# Power.net
KiCad netlist of a schematic drawn in Altium Designer
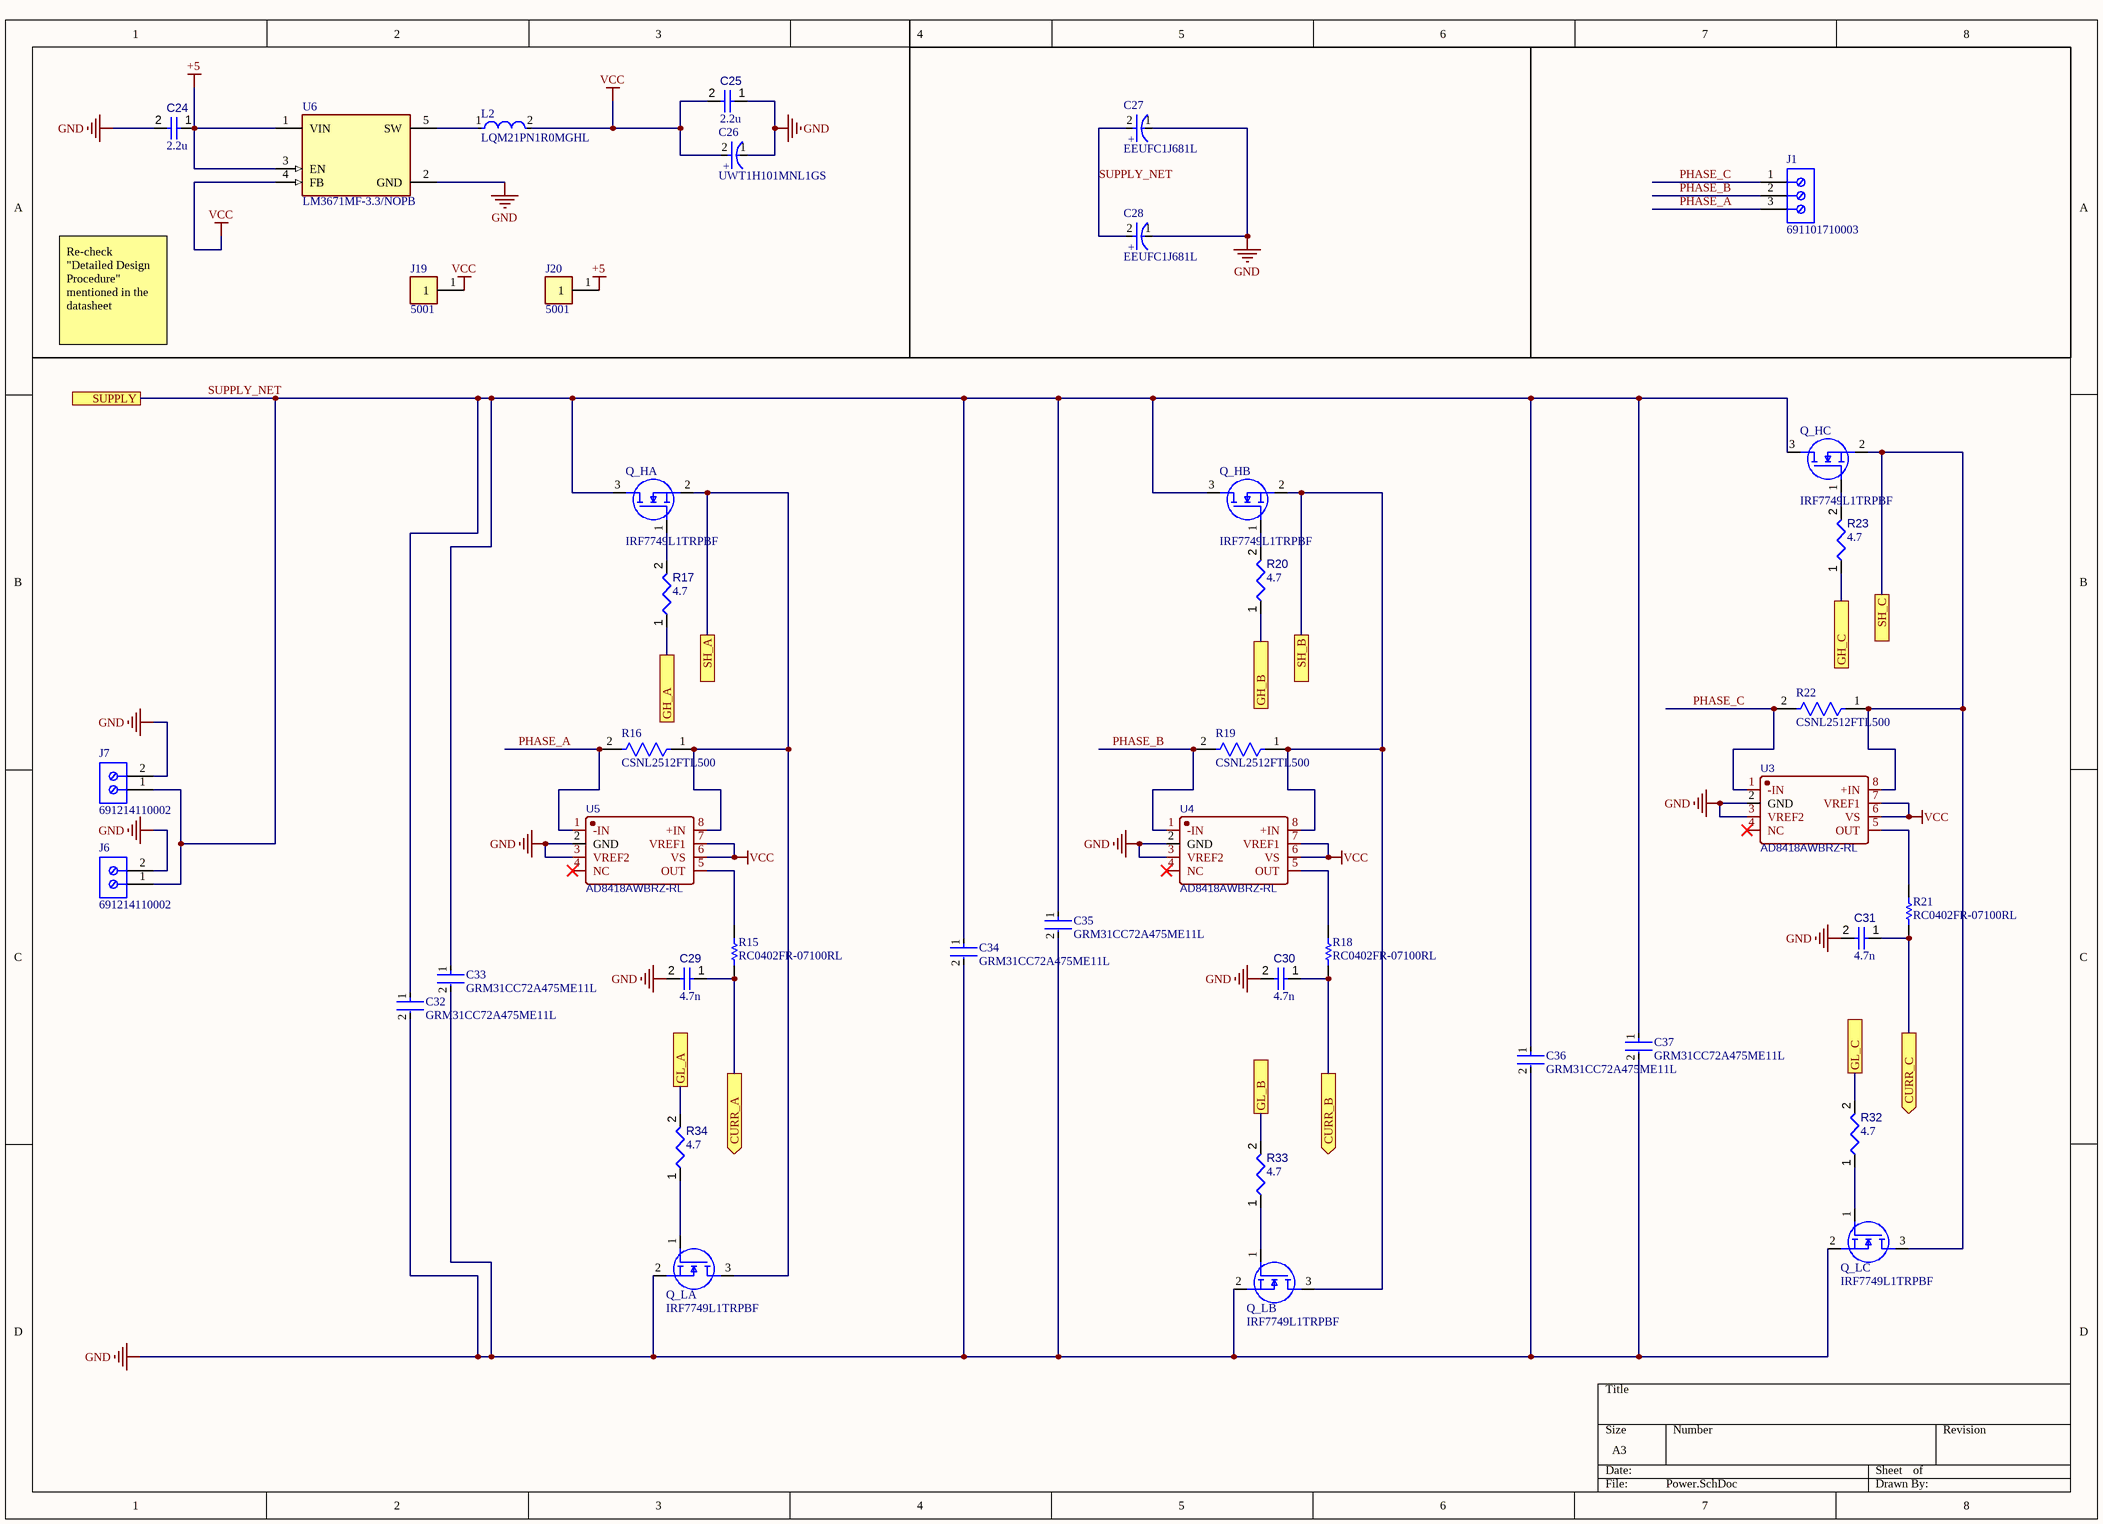
[diagram p0: Power.SchDoc]

(export (version "E")
  (design (tool "Eeschema 10.0.6"))
  (components
    (comp (ref "C24")
      (value "2.2u")
      (footprint "CAP-0805")
      (description "ESD SMD Comm X7R 0805 (2012Metric) Ceramic Capacitor 0.079Lx0.049W 2.00mmx1.25mm X7R ±5% 2.2muF")
      (fields (field (name "Comment") "C0805C225J4REC7800"))
      (libsource (lib "University of Michigan") (part "CAP-NP-2"))
    )
    (comp (ref "C25")
      (value "2.2u")
      (footprint "CAP-0805")
      (description "ESD SMD Comm X7R 0805 (2012Metric) Ceramic Capacitor 0.079Lx0.049W 2.00mmx1.25mm X7R ±5% 2.2muF")
      (fields (field (name "Comment") "C0805C225J4REC7800"))
      (libsource (lib "University of Michigan") (part "CAP-NP-2"))
    )
    (comp (ref "C26")
      (value "UWT1H101MNL1GS")
      (footprint "FP-UWT1H101MNL1GS-MFG")
      (description "CAP ALUM 100UF 20% 50V SMD")
      (fields (field (name "TOLERANCE") "20%") (field (name "VOLTAGE") "50V"))
      (libsource (lib "Altium Content Vault") (part "203bc49f2ac43e59fd269a8c329ed05"))
    )
    (comp (ref "C27")
      (value "EEUFC1J681L")
      (footprint "FP-EEUFC1J681L-MFG")
      (description "CAP ALUM 680UF 20% 63V RADIAL")
      (fields
        (field (name "MANUFACTURER") "Panasonic")
        (field (name "OCTOPART") "https://octopart.com/eeu-fc1j681l-panasonic-39478579")
      )
      (libsource (lib "Altium Content Vault") (part "cf48714ba7e38822c1575c7ec0b6d1f"))
    )
    (comp (ref "C28")
      (value "EEUFC1J681L")
      (footprint "FP-EEUFC1J681L-MFG")
      (description "CAP ALUM 680UF 20% 63V RADIAL")
      (fields
        (field (name "MANUFACTURER") "Panasonic")
        (field (name "OCTOPART") "https://octopart.com/eeu-fc1j681l-panasonic-39478579")
      )
      (libsource (lib "Altium Content Vault") (part "cf48714ba7e38822c1575c7ec0b6d1f"))
    )
    (comp (ref "C29")
      (value "4.7n")
      (footprint "CAP-0402")
      (fields (field (name "Comment") "C0402C472K4RECAUTO"))
      (libsource (lib "University of Michigan") (part "CAP-NP-2"))
    )
    (comp (ref "C30")
      (value "4.7n")
      (footprint "CAP-0402")
      (fields (field (name "Comment") "C0402C472K4RECAUTO"))
      (libsource (lib "University of Michigan") (part "CAP-NP-2"))
    )
    (comp (ref "C31")
      (value "4.7n")
      (footprint "CAP-0402")
      (fields (field (name "Comment") "C0402C472K4RECAUTO"))
      (libsource (lib "University of Michigan") (part "CAP-NP-2"))
    )
    (comp (ref "C32")
      (value "GRM31CC72A475ME11L")
      (footprint "FP-GRM31C-0_3-e0_3_0_9-MFG")
      (description "Chip Multilayer Ceramic Capacitors for General Purpose, 1206, 4.7uF, X7S, 22%, 20%, 100V")
      (libsource (lib "Altium Content Vault") (part "11868f565c42a9108669ba33697ecf6"))
    )
    (comp (ref "C33")
      (value "GRM31CC72A475ME11L")
      (footprint "FP-GRM31C-0_3-e0_3_0_9-MFG")
      (description "Chip Multilayer Ceramic Capacitors for General Purpose, 1206, 4.7uF, X7S, 22%, 20%, 100V")
      (libsource (lib "Altium Content Vault") (part "11868f565c42a9108669ba33697ecf6"))
    )
    (comp (ref "C34")
      (value "GRM31CC72A475ME11L")
      (footprint "FP-GRM31C-0_3-e0_3_0_9-MFG")
      (description "Chip Multilayer Ceramic Capacitors for General Purpose, 1206, 4.7uF, X7S, 22%, 20%, 100V")
      (libsource (lib "Altium Content Vault") (part "11868f565c42a9108669ba33697ecf6"))
    )
    (comp (ref "C35")
      (value "GRM31CC72A475ME11L")
      (footprint "FP-GRM31C-0_3-e0_3_0_9-MFG")
      (description "Chip Multilayer Ceramic Capacitors for General Purpose, 1206, 4.7uF, X7S, 22%, 20%, 100V")
      (libsource (lib "Altium Content Vault") (part "11868f565c42a9108669ba33697ecf6"))
    )
    (comp (ref "C36")
      (value "GRM31CC72A475ME11L")
      (footprint "FP-GRM31C-0_3-e0_3_0_9-MFG")
      (description "Chip Multilayer Ceramic Capacitors for General Purpose, 1206, 4.7uF, X7S, 22%, 20%, 100V")
      (libsource (lib "Altium Content Vault") (part "11868f565c42a9108669ba33697ecf6"))
    )
    (comp (ref "C37")
      (value "GRM31CC72A475ME11L")
      (footprint "FP-GRM31C-0_3-e0_3_0_9-MFG")
      (description "Chip Multilayer Ceramic Capacitors for General Purpose, 1206, 4.7uF, X7S, 22%, 20%, 100V")
      (libsource (lib "Altium Content Vault") (part "11868f565c42a9108669ba33697ecf6"))
    )
    (comp (ref "J1")
      (value "691101710003")
      (footprint "691101710003")
      (fields (field (name "VOLTAGE") "250V"))
      (libsource (lib "Altium Content Vault") (part "TBL - 1R - 03P - Screw"))
    )
    (comp (ref "J6")
      (value "691214110002")
      (footprint "691214110002")
      (fields (field (name "VOLTAGE") "300V"))
      (libsource (lib "Altium Content Vault") (part "TBL - 1R - 02P - Screw"))
    )
    (comp (ref "J7")
      (value "691214110002")
      (footprint "691214110002")
      (fields (field (name "VOLTAGE") "300V"))
      (libsource (lib "Altium Content Vault") (part "TBL - 1R - 02P - Screw"))
    )
    (comp (ref "J19")
      (value "5001")
      (footprint "FP-5001-MFG")
      (description "PC TEST POINT MINIATURE BLACK")
      (libsource (lib "Altium Content Vault") (part "1e4615820a309e3ce90f9e6d957b7fa"))
    )
    (comp (ref "J20")
      (value "5001")
      (footprint "FP-5001-MFG")
      (description "PC TEST POINT MINIATURE BLACK")
      (libsource (lib "Altium Content Vault") (part "1e4615820a309e3ce90f9e6d957b7fa"))
    )
    (comp (ref "L2")
      (value "LQM21PN1R0MGHL")
      (footprint "FP-LQM21PH_G0-MFG")
      (description "Multilayer Type Inductor for Power Lines, 0805 (2012), 1μH, 20%, 0.1Ω, 2A")
      (fields (field (name "TOLERANCE") "20%"))
      (libsource (lib "Altium Content Vault") (part "725321dda6339637d4d059423bc1c3c"))
    )
    (comp (ref "Q_HA")
      (value "IRF7749L1TRPBF")
      (footprint "IC-MOSFET-DirectFET")
      (description "Power Field-Effect Transistor, 375A I(D), 1-Element, N-Channel, Metal-oxide Semiconductor FET")
      (libsource (lib "University of Michigan") (part "NMOS-200MA-0001"))
    )
    (comp (ref "Q_HB")
      (value "IRF7749L1TRPBF")
      (footprint "IC-MOSFET-DirectFET")
      (description "Power Field-Effect Transistor, 375A I(D), 1-Element, N-Channel, Metal-oxide Semiconductor FET")
      (libsource (lib "University of Michigan") (part "NMOS-200MA-0001"))
    )
    (comp (ref "Q_HC")
      (value "IRF7749L1TRPBF")
      (footprint "IC-MOSFET-DirectFET")
      (description "Power Field-Effect Transistor, 375A I(D), 1-Element, N-Channel, Metal-oxide Semiconductor FET")
      (libsource (lib "University of Michigan") (part "NMOS-200MA-0001"))
    )
    (comp (ref "Q_LA")
      (value "IRF7749L1TRPBF")
      (footprint "IC-MOSFET-DirectFET")
      (description "Power Field-Effect Transistor, 375A I(D), 1-Element, N-Channel, Metal-oxide Semiconductor FET")
      (libsource (lib "University of Michigan") (part "NMOS-200MA-0001"))
    )
    (comp (ref "Q_LB")
      (value "IRF7749L1TRPBF")
      (footprint "IC-MOSFET-DirectFET")
      (description "Power Field-Effect Transistor, 375A I(D), 1-Element, N-Channel, Metal-oxide Semiconductor FET")
      (libsource (lib "University of Michigan") (part "NMOS-200MA-0001"))
    )
    (comp (ref "Q_LC")
      (value "IRF7749L1TRPBF")
      (footprint "IC-MOSFET-DirectFET")
      (description "Power Field-Effect Transistor, 375A I(D), 1-Element, N-Channel, Metal-oxide Semiconductor FET")
      (libsource (lib "University of Michigan") (part "NMOS-200MA-0001"))
    )
    (comp (ref "R15")
      (value "RC0402FR-07100RL")
      (footprint "RESC1005X40X25ML05T10")
      (fields (field (name "MANUFACTURER") "Yageo / Phycomp"))
      (libsource (lib "Altium Content Vault") (part "RES"))
    )
    (comp (ref "R16")
      (value "CSNL2512FTL500")
      (footprint "FP-CSNL2512FTL500-MFG")
      (description "RES 500 UOHM 1% 2W 2512")
      (fields (field (name "TOLERANCE") "1%"))
      (libsource (lib "Altium Content Vault") (part "1029c3af85768c4190bb7ad29bc67b5"))
    )
    (comp (ref "R17")
      (value "4.7")
      (footprint "RES-0603")
      (fields
        (field (name "POWER") "250mW")
        (field (name "TOLERANCE") "5%")
        (field (name "Comment") "CRCW06034R70JNEAHP")
      )
      (libsource (lib "University of Michigan") (part "RES-2"))
    )
    (comp (ref "R18")
      (value "RC0402FR-07100RL")
      (footprint "RESC1005X40X25ML05T10")
      (fields (field (name "MANUFACTURER") "Yageo / Phycomp"))
      (libsource (lib "Altium Content Vault") (part "RES"))
    )
    (comp (ref "R19")
      (value "CSNL2512FTL500")
      (footprint "FP-CSNL2512FTL500-MFG")
      (description "RES 500 UOHM 1% 2W 2512")
      (fields (field (name "TOLERANCE") "1%"))
      (libsource (lib "Altium Content Vault") (part "1029c3af85768c4190bb7ad29bc67b5"))
    )
    (comp (ref "R20")
      (value "4.7")
      (footprint "RES-0603")
      (fields
        (field (name "POWER") "250mW")
        (field (name "TOLERANCE") "5%")
        (field (name "Comment") "CRCW06034R70JNEAHP")
      )
      (libsource (lib "University of Michigan") (part "RES-2"))
    )
    (comp (ref "R21")
      (value "RC0402FR-07100RL")
      (footprint "RESC1005X40X25ML05T10")
      (fields (field (name "MANUFACTURER") "Yageo / Phycomp"))
      (libsource (lib "Altium Content Vault") (part "RES"))
    )
    (comp (ref "R22")
      (value "CSNL2512FTL500")
      (footprint "FP-CSNL2512FTL500-MFG")
      (description "RES 500 UOHM 1% 2W 2512")
      (fields (field (name "TOLERANCE") "1%"))
      (libsource (lib "Altium Content Vault") (part "1029c3af85768c4190bb7ad29bc67b5"))
    )
    (comp (ref "R23")
      (value "4.7")
      (footprint "RES-0603")
      (fields
        (field (name "POWER") "250mW")
        (field (name "TOLERANCE") "5%")
        (field (name "Comment") "CRCW06034R70JNEAHP")
      )
      (libsource (lib "University of Michigan") (part "RES-2"))
    )
    (comp (ref "R32")
      (value "4.7")
      (footprint "RES-0603")
      (fields
        (field (name "POWER") "250mW")
        (field (name "TOLERANCE") "5%")
        (field (name "Comment") "CRCW06034R70JNEAHP")
      )
      (libsource (lib "University of Michigan") (part "RES-2"))
    )
    (comp (ref "R33")
      (value "4.7")
      (footprint "RES-0603")
      (fields
        (field (name "POWER") "250mW")
        (field (name "TOLERANCE") "5%")
        (field (name "Comment") "CRCW06034R70JNEAHP")
      )
      (libsource (lib "University of Michigan") (part "RES-2"))
    )
    (comp (ref "R34")
      (value "4.7")
      (footprint "RES-0603")
      (fields
        (field (name "POWER") "250mW")
        (field (name "TOLERANCE") "5%")
        (field (name "Comment") "CRCW06034R70JNEAHP")
      )
      (libsource (lib "University of Michigan") (part "RES-2"))
    )
    (comp (ref "U3")
      (value "AD8418AWBRZ-RL")
      (footprint "MasterLib:IC-SOIC8")
      (fields (field (name "MANUFACTURER") "Analog Devices") (field (name "CONTRIBUTOR") "LCSC"))
      (libsource (lib "altium-import") (part "root_0_AD8418AWBRZ-RL_"))
    )
    (comp (ref "U4")
      (value "AD8418AWBRZ-RL")
      (footprint "MasterLib:IC-SOIC8")
      (fields (field (name "MANUFACTURER") "Analog Devices") (field (name "CONTRIBUTOR") "LCSC"))
      (libsource (lib "altium-import") (part "root_0_AD8418AWBRZ-RL_"))
    )
    (comp (ref "U5")
      (value "AD8418AWBRZ-RL")
      (footprint "MasterLib:IC-SOIC8")
      (fields (field (name "MANUFACTURER") "Analog Devices") (field (name "CONTRIBUTOR") "LCSC"))
      (libsource (lib "altium-import") (part "root_0_AD8418AWBRZ-RL_"))
    )
    (comp (ref "U6")
      (value "LM3671MF-3.3/NOPB")
      (footprint "FP-DBV0005A-IPC_C")
      (description "IC REG BUCK 3.3V 600MA SOT23-5")
      (libsource (lib "Altium Content Vault") (part "6d197bdb01e3056b44211661dc106cd"))
    )
  )
  (nets
    (net (code "1") (name "+5") (class "Default")
      (node (ref "C24") (pin "1") (pinfunction "1_1") (pintype "passive"))
      (node (ref "J20") (pin "1") (pinfunction "1_1") (pintype "passive"))
      (node (ref "U6") (pin "1") (pinfunction "VIN_1") (pintype "power_in"))
      (node (ref "U6") (pin "3") (pinfunction "EN_3") (pintype "input"))
    )
    (net (code "2") (name "/CURR_A") (class "Default")
      (node (ref "C29") (pin "1") (pinfunction "1_1") (pintype "passive"))
      (node (ref "R15") (pin "1") (pinfunction "1_1") (pintype "passive"))
    )
    (net (code "3") (name "/CURR_B") (class "Default")
      (node (ref "C30") (pin "1") (pinfunction "1_1") (pintype "passive"))
      (node (ref "R18") (pin "1") (pinfunction "1_1") (pintype "passive"))
    )
    (net (code "4") (name "/CURR_C") (class "Default")
      (node (ref "C31") (pin "1") (pinfunction "1_1") (pintype "passive"))
      (node (ref "R21") (pin "1") (pinfunction "1_1") (pintype "passive"))
    )
    (net (code "5") (name "/GH_A") (class "Default")
      (node (ref "R17") (pin "1") (pinfunction "1_1") (pintype "passive"))
    )
    (net (code "6") (name "/GH_B") (class "Default")
      (node (ref "R20") (pin "1") (pinfunction "1_1") (pintype "passive"))
    )
    (net (code "7") (name "/GH_C") (class "Default")
      (node (ref "R23") (pin "1") (pinfunction "1_1") (pintype "passive"))
    )
    (net (code "8") (name "/GL_A") (class "Default")
      (node (ref "R34") (pin "2") (pinfunction "2_2") (pintype "passive"))
    )
    (net (code "9") (name "/GL_B") (class "Default")
      (node (ref "R33") (pin "2") (pinfunction "2_2") (pintype "passive"))
    )
    (net (code "10") (name "/GL_C") (class "Default")
      (node (ref "R32") (pin "2") (pinfunction "2_2") (pintype "passive"))
    )
    (net (code "11") (name "/PHASE_A") (class "Default")
      (node (ref "J1") (pin "3") (pinfunction "3_3") (pintype "passive"))
      (node (ref "R16") (pin "2") (pinfunction "2_2") (pintype "passive"))
      (node (ref "U5") (pin "1") (pinfunction "-IN_1") (pintype "passive"))
    )
    (net (code "12") (name "/PHASE_B") (class "Default")
      (node (ref "J1") (pin "2") (pinfunction "2_2") (pintype "passive"))
      (node (ref "R19") (pin "2") (pinfunction "2_2") (pintype "passive"))
      (node (ref "U4") (pin "1") (pinfunction "-IN_1") (pintype "passive"))
    )
    (net (code "13") (name "/PHASE_C") (class "Default")
      (node (ref "J1") (pin "1") (pinfunction "1_1") (pintype "passive"))
      (node (ref "R22") (pin "2") (pinfunction "2_2") (pintype "passive"))
      (node (ref "U3") (pin "1") (pinfunction "-IN_1") (pintype "passive"))
    )
    (net (code "14") (name "/SH_A") (class "Default")
      (node (ref "Q_HA") (pin "2") (pinfunction "S_2") (pintype "passive"))
      (node (ref "Q_LA") (pin "3") (pinfunction "D_3") (pintype "passive"))
      (node (ref "R16") (pin "1") (pinfunction "1_1") (pintype "passive"))
      (node (ref "U5") (pin "8") (pinfunction "+IN_8") (pintype "passive"))
    )
    (net (code "15") (name "/SH_B") (class "Default")
      (node (ref "Q_HB") (pin "2") (pinfunction "S_2") (pintype "passive"))
      (node (ref "Q_LB") (pin "3") (pinfunction "D_3") (pintype "passive"))
      (node (ref "R19") (pin "1") (pinfunction "1_1") (pintype "passive"))
      (node (ref "U4") (pin "8") (pinfunction "+IN_8") (pintype "passive"))
    )
    (net (code "16") (name "/SH_C") (class "Default")
      (node (ref "Q_HC") (pin "2") (pinfunction "S_2") (pintype "passive"))
      (node (ref "Q_LC") (pin "3") (pinfunction "D_3") (pintype "passive"))
      (node (ref "R22") (pin "1") (pinfunction "1_1") (pintype "passive"))
      (node (ref "U3") (pin "8") (pinfunction "+IN_8") (pintype "passive"))
    )
    (net (code "17") (name "/SUPPLY_NET") (class "Default")
      (node (ref "C27") (pin "2") (pinfunction "A_2") (pintype "passive"))
      (node (ref "C28") (pin "2") (pinfunction "A_2") (pintype "passive"))
      (node (ref "C32") (pin "1") (pinfunction "1_1") (pintype "passive"))
      (node (ref "C33") (pin "1") (pinfunction "1_1") (pintype "passive"))
      (node (ref "C34") (pin "1") (pinfunction "1_1") (pintype "passive"))
      (node (ref "C35") (pin "1") (pinfunction "1_1") (pintype "passive"))
      (node (ref "C36") (pin "1") (pinfunction "1_1") (pintype "passive"))
      (node (ref "C37") (pin "1") (pinfunction "1_1") (pintype "passive"))
      (node (ref "J6") (pin "1") (pinfunction "1_1") (pintype "passive"))
      (node (ref "J7") (pin "1") (pinfunction "1_1") (pintype "passive"))
      (node (ref "Q_HA") (pin "3") (pinfunction "D_3") (pintype "passive"))
      (node (ref "Q_HB") (pin "3") (pinfunction "D_3") (pintype "passive"))
      (node (ref "Q_HC") (pin "3") (pinfunction "D_3") (pintype "passive"))
    )
    (net (code "18") (name "GND") (class "Default")
      (node (ref "C24") (pin "2") (pinfunction "2_2") (pintype "passive"))
      (node (ref "C25") (pin "1") (pinfunction "1_1") (pintype "passive"))
      (node (ref "C26") (pin "1") (pinfunction "C_1") (pintype "passive"))
      (node (ref "C27") (pin "1") (pinfunction "C_1") (pintype "passive"))
      (node (ref "C28") (pin "1") (pinfunction "C_1") (pintype "passive"))
      (node (ref "C29") (pin "2") (pinfunction "2_2") (pintype "passive"))
      (node (ref "C30") (pin "2") (pinfunction "2_2") (pintype "passive"))
      (node (ref "C31") (pin "2") (pinfunction "2_2") (pintype "passive"))
      (node (ref "C32") (pin "2") (pinfunction "2_2") (pintype "passive"))
      (node (ref "C33") (pin "2") (pinfunction "2_2") (pintype "passive"))
      (node (ref "C34") (pin "2") (pinfunction "2_2") (pintype "passive"))
      (node (ref "C35") (pin "2") (pinfunction "2_2") (pintype "passive"))
      (node (ref "C36") (pin "2") (pinfunction "2_2") (pintype "passive"))
      (node (ref "C37") (pin "2") (pinfunction "2_2") (pintype "passive"))
      (node (ref "J6") (pin "2") (pinfunction "2_2") (pintype "passive"))
      (node (ref "J7") (pin "2") (pinfunction "2_2") (pintype "passive"))
      (node (ref "Q_LA") (pin "2") (pinfunction "S_2") (pintype "passive"))
      (node (ref "Q_LB") (pin "2") (pinfunction "S_2") (pintype "passive"))
      (node (ref "Q_LC") (pin "2") (pinfunction "S_2") (pintype "passive"))
      (node (ref "U3") (pin "2") (pinfunction "GND_2") (pintype "passive"))
      (node (ref "U3") (pin "3") (pinfunction "VREF2_3") (pintype "passive"))
      (node (ref "U4") (pin "2") (pinfunction "GND_2") (pintype "passive"))
      (node (ref "U4") (pin "3") (pinfunction "VREF2_3") (pintype "passive"))
      (node (ref "U5") (pin "2") (pinfunction "GND_2") (pintype "passive"))
      (node (ref "U5") (pin "3") (pinfunction "VREF2_3") (pintype "passive"))
      (node (ref "U6") (pin "2") (pinfunction "GND_2") (pintype "power_in"))
    )
    (net (code "19") (name "Net-(Q_HA-G)") (class "Default")
      (node (ref "Q_HA") (pin "1") (pinfunction "G_1") (pintype "passive"))
      (node (ref "R17") (pin "2") (pinfunction "2_2") (pintype "passive"))
    )
    (net (code "20") (name "Net-(Q_HB-G)") (class "Default")
      (node (ref "Q_HB") (pin "1") (pinfunction "G_1") (pintype "passive"))
      (node (ref "R20") (pin "2") (pinfunction "2_2") (pintype "passive"))
    )
    (net (code "21") (name "Net-(Q_HC-G)") (class "Default")
      (node (ref "Q_HC") (pin "1") (pinfunction "G_1") (pintype "passive"))
      (node (ref "R23") (pin "2") (pinfunction "2_2") (pintype "passive"))
    )
    (net (code "22") (name "Net-(Q_LA-G)") (class "Default")
      (node (ref "Q_LA") (pin "1") (pinfunction "G_1") (pintype "passive"))
      (node (ref "R34") (pin "1") (pinfunction "1_1") (pintype "passive"))
    )
    (net (code "23") (name "Net-(Q_LB-G)") (class "Default")
      (node (ref "Q_LB") (pin "1") (pinfunction "G_1") (pintype "passive"))
      (node (ref "R33") (pin "1") (pinfunction "1_1") (pintype "passive"))
    )
    (net (code "24") (name "Net-(Q_LC-G)") (class "Default")
      (node (ref "Q_LC") (pin "1") (pinfunction "G_1") (pintype "passive"))
      (node (ref "R32") (pin "1") (pinfunction "1_1") (pintype "passive"))
    )
    (net (code "25") (name "Net-(U3-OUT)") (class "Default")
      (node (ref "R21") (pin "2") (pinfunction "2_2") (pintype "passive"))
      (node (ref "U3") (pin "5") (pinfunction "OUT_5") (pintype "passive"))
    )
    (net (code "26") (name "Net-(U4-OUT)") (class "Default")
      (node (ref "R18") (pin "2") (pinfunction "2_2") (pintype "passive"))
      (node (ref "U4") (pin "5") (pinfunction "OUT_5") (pintype "passive"))
    )
    (net (code "27") (name "Net-(U5-OUT)") (class "Default")
      (node (ref "R15") (pin "2") (pinfunction "2_2") (pintype "passive"))
      (node (ref "U5") (pin "5") (pinfunction "OUT_5") (pintype "passive"))
    )
    (net (code "28") (name "Net-(U6-SW)") (class "Default")
      (node (ref "L2") (pin "1") (pinfunction "1_1") (pintype "passive"))
      (node (ref "U6") (pin "5") (pinfunction "SW_5") (pintype "power_in"))
    )
    (net (code "29") (name "VCC") (class "Default")
      (node (ref "C25") (pin "2") (pinfunction "2_2") (pintype "passive"))
      (node (ref "C26") (pin "2") (pinfunction "A_2") (pintype "passive"))
      (node (ref "J19") (pin "1") (pinfunction "1_1") (pintype "passive"))
      (node (ref "L2") (pin "2") (pinfunction "2_2") (pintype "passive"))
      (node (ref "U3") (pin "6") (pinfunction "VS_6") (pintype "passive"))
      (node (ref "U3") (pin "7") (pinfunction "VREF1_7") (pintype "passive"))
      (node (ref "U4") (pin "6") (pinfunction "VS_6") (pintype "passive"))
      (node (ref "U4") (pin "7") (pinfunction "VREF1_7") (pintype "passive"))
      (node (ref "U5") (pin "6") (pinfunction "VS_6") (pintype "passive"))
      (node (ref "U5") (pin "7") (pinfunction "VREF1_7") (pintype "passive"))
      (node (ref "U6") (pin "4") (pinfunction "FB_4") (pintype "input"))
    )
    (net (code "30") (name "unconnected-(U3-NC-Pad4)") (class "Default")
      (node (ref "U3") (pin "4") (pinfunction "NC_4") (pintype "passive+no_connect"))
    )
    (net (code "31") (name "unconnected-(U4-NC-Pad4)") (class "Default")
      (node (ref "U4") (pin "4") (pinfunction "NC_4") (pintype "passive+no_connect"))
    )
    (net (code "32") (name "unconnected-(U5-NC-Pad4)") (class "Default")
      (node (ref "U5") (pin "4") (pinfunction "NC_4") (pintype "passive+no_connect"))
    )
  )
)
